# 1_123456_01.net
KiCad netlist of a schematic drawn in Altium Designer
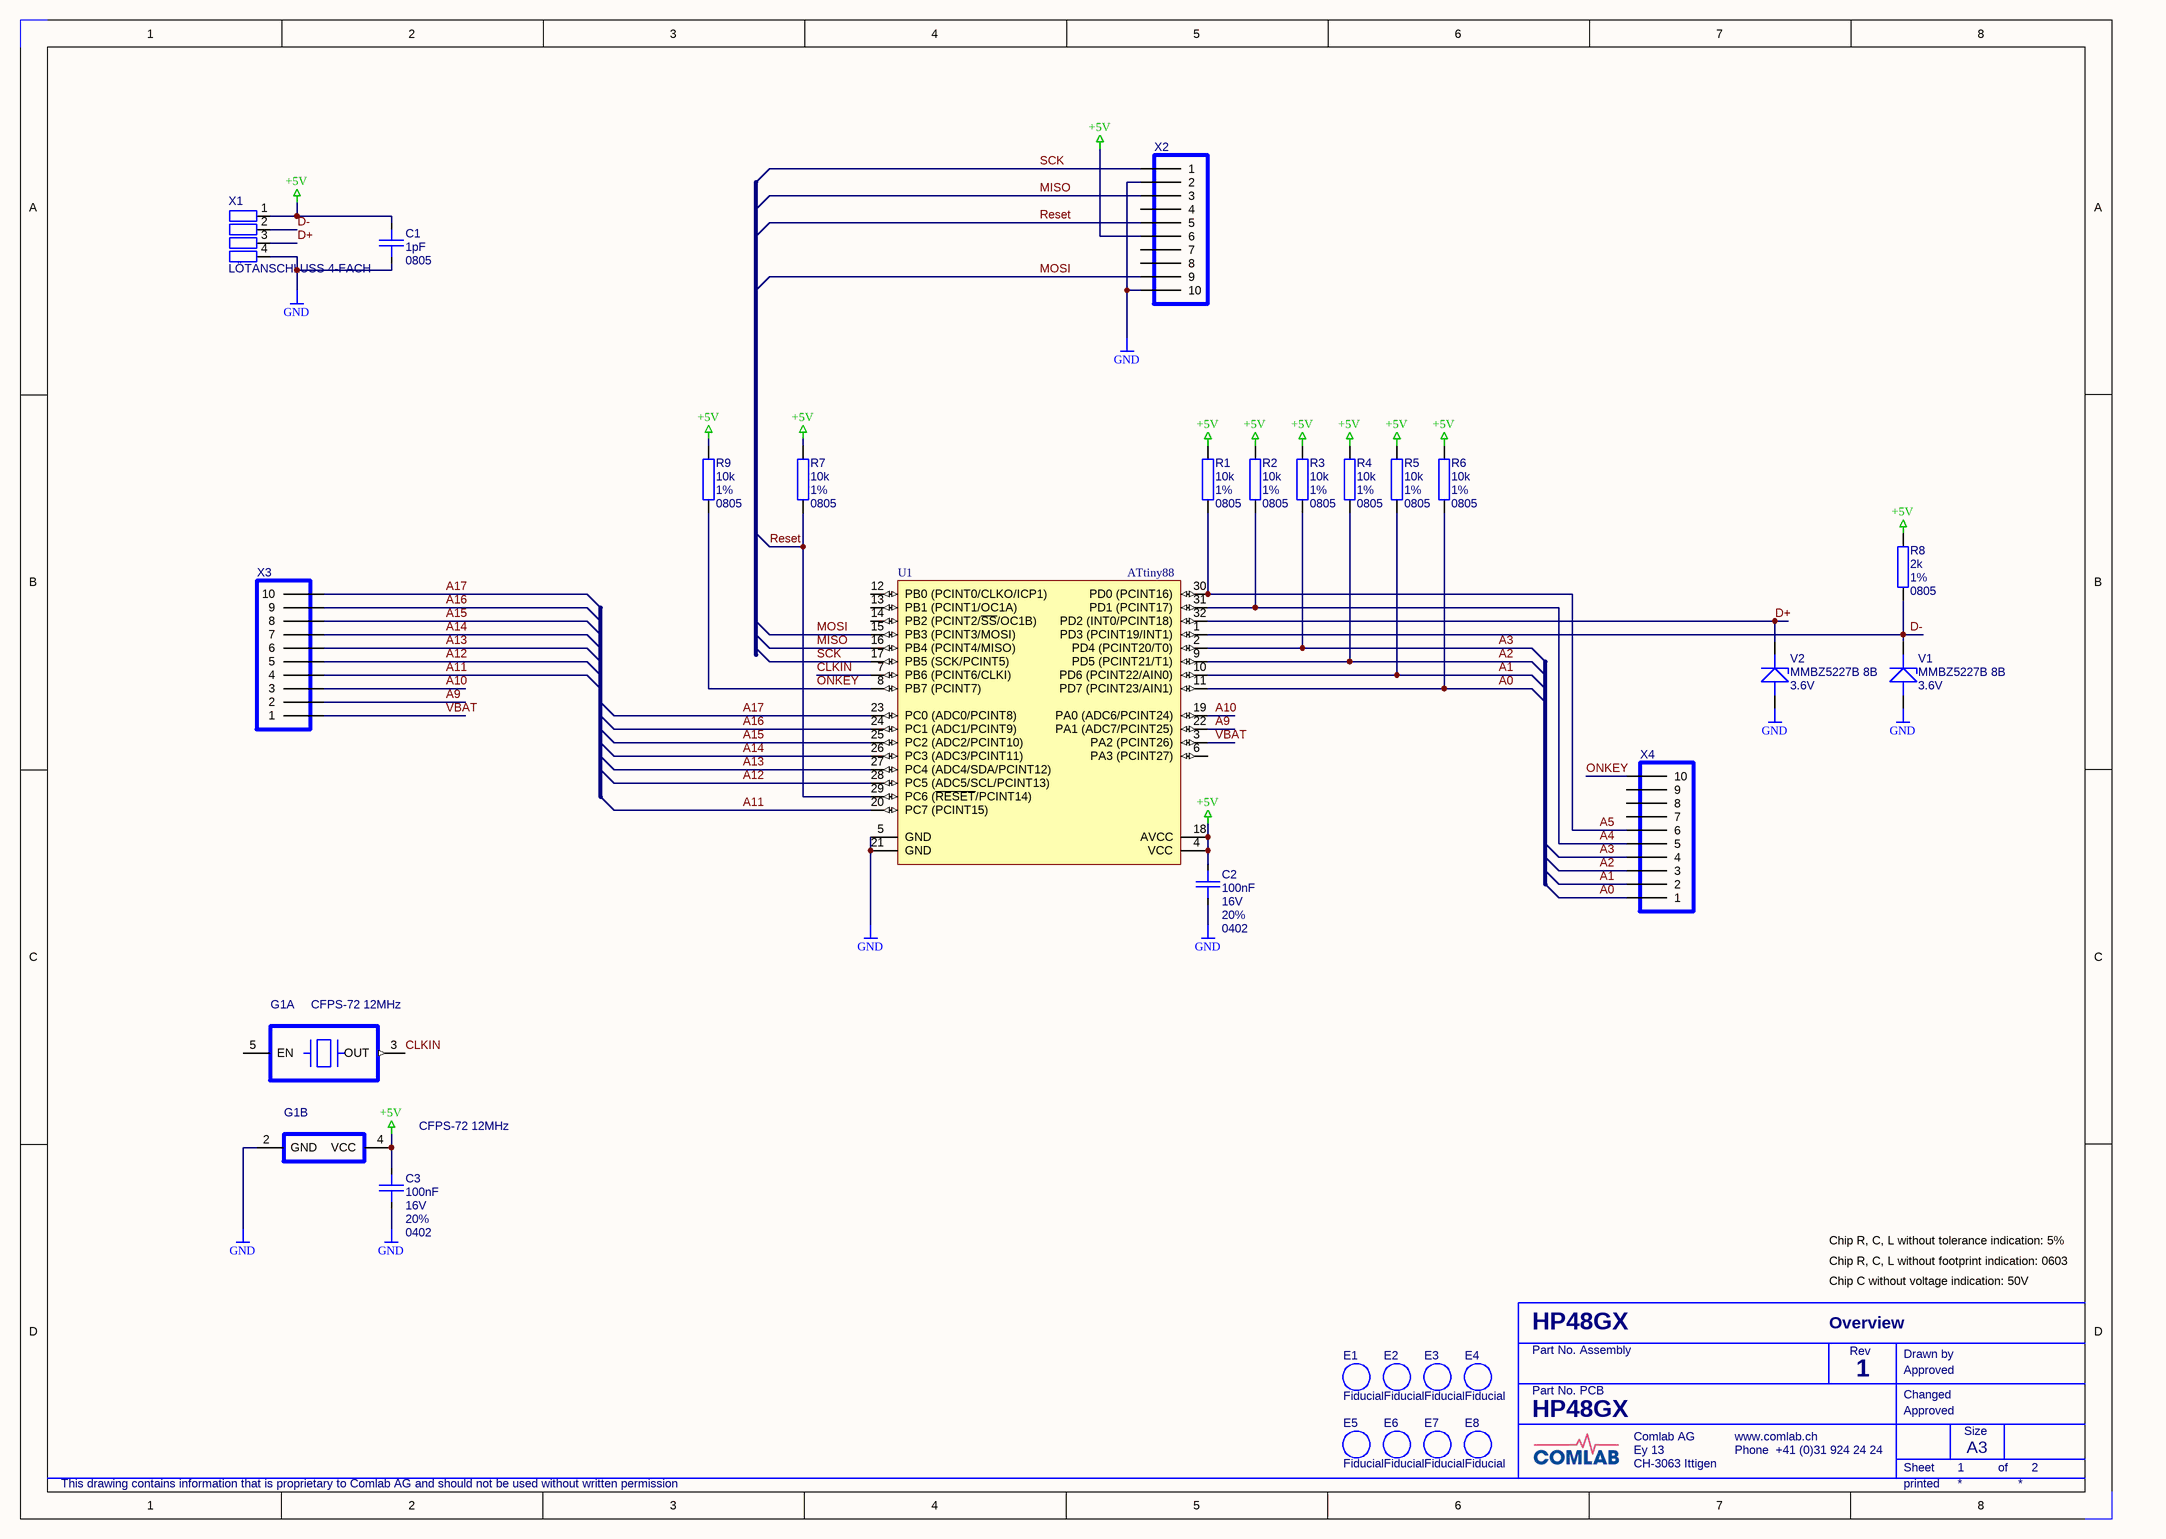
[diagram p0: 1_123456_01.SchDoc]

(export (version "E")
  (design (tool "Eeschema 10.0.6"))
  (components
    (comp (ref "C1")
      (value "1pF")
      (footprint "0805")
      (description "Kond/Chip-Kondensator")
      (libsource (lib "Library Comlab") (part "(1pF  0805  15.00064"))
    )
    (comp (ref "C2")
      (value "100nF")
      (footprint "0402")
      (description "Kond/Chip-Kondensator")
      (fields (field (name "SPANNUNG") "16V") (field (name "TOLERANZ") "20%"))
      (libsource (lib "HP48GX_01_1") (part "1uF  0402  118194"))
    )
    (comp (ref "C3")
      (value "100nF")
      (footprint "0402")
      (description "Kond/Chip-Kondensator")
      (fields (field (name "SPANNUNG") "16V") (field (name "TOLERANZ") "20%"))
      (libsource (lib "HP48GX_01_1") (part "1uF  0402  118194"))
    )
    (comp (ref "E1")
      (value "Fiducial")
      (footprint "ZENTRIER Fiducial")
      (description "Zubehör/Zentriermarke, 2...8x diagonal auf jedem Print")
      (libsource (lib "Library Comlab") (part "ZENTRIERMARKE Fiducial"))
    )
    (comp (ref "E2")
      (value "Fiducial")
      (footprint "ZENTRIER Fiducial")
      (description "Zubehör/Zentriermarke, 2...8x diagonal auf jedem Print")
      (libsource (lib "Library Comlab") (part "ZENTRIERMARKE Fiducial"))
    )
    (comp (ref "E3")
      (value "Fiducial")
      (footprint "ZENTRIER Fiducial")
      (description "Zubehör/Zentriermarke, 2...8x diagonal auf jedem Print")
      (libsource (lib "Library Comlab") (part "ZENTRIERMARKE Fiducial"))
    )
    (comp (ref "E4")
      (value "Fiducial")
      (footprint "ZENTRIER Fiducial")
      (description "Zubehör/Zentriermarke, 2...8x diagonal auf jedem Print")
      (libsource (lib "Library Comlab") (part "ZENTRIERMARKE Fiducial"))
    )
    (comp (ref "E5")
      (value "Fiducial")
      (footprint "ZENTRIER Fiducial")
      (description "Zubehör/Zentriermarke, 2...8x diagonal auf jedem Print")
      (libsource (lib "Library Comlab") (part "ZENTRIERMARKE Fiducial"))
    )
    (comp (ref "E6")
      (value "Fiducial")
      (footprint "ZENTRIER Fiducial")
      (description "Zubehör/Zentriermarke, 2...8x diagonal auf jedem Print")
      (libsource (lib "Library Comlab") (part "ZENTRIERMARKE Fiducial"))
    )
    (comp (ref "E7")
      (value "Fiducial")
      (footprint "ZENTRIER Fiducial")
      (description "Zubehör/Zentriermarke, 2...8x diagonal auf jedem Print")
      (libsource (lib "Library Comlab") (part "ZENTRIERMARKE Fiducial"))
    )
    (comp (ref "E8")
      (value "Fiducial")
      (footprint "ZENTRIER Fiducial")
      (description "Zubehör/Zentriermarke, 2...8x diagonal auf jedem Print")
      (libsource (lib "Library Comlab") (part "ZENTRIERMARKE Fiducial"))
    )
    (comp (ref "G1")
      (value "CFPS-72 12MHz")
      (footprint "TW0203A")
      (description "RF/OSZI")
      (libsource (lib "") (part "OSZI{colon} 8MHz TW0203  TW0203A  117861_1"))
    )
    (comp (ref "R1")
      (value "10k")
      (footprint "0805")
      (description "Wid/Chip-Widerstand")
      (fields (field (name "TOLERANZ") "1%"))
      (libsource (lib "Library Comlab") (part "(1K  0805  14.00130"))
    )
    (comp (ref "R2")
      (value "10k")
      (footprint "0805")
      (description "Wid/Chip-Widerstand")
      (fields (field (name "TOLERANZ") "1%"))
      (libsource (lib "Library Comlab") (part "(1K  0805  14.00130"))
    )
    (comp (ref "R3")
      (value "10k")
      (footprint "0805")
      (description "Wid/Chip-Widerstand")
      (fields (field (name "TOLERANZ") "1%"))
      (libsource (lib "Library Comlab") (part "(1K  0805  14.00130"))
    )
    (comp (ref "R4")
      (value "10k")
      (footprint "0805")
      (description "Wid/Chip-Widerstand")
      (fields (field (name "TOLERANZ") "1%"))
      (libsource (lib "Library Comlab") (part "(1K  0805  14.00130"))
    )
    (comp (ref "R5")
      (value "10k")
      (footprint "0805")
      (description "Wid/Chip-Widerstand")
      (fields (field (name "TOLERANZ") "1%"))
      (libsource (lib "Library Comlab") (part "(1K  0805  14.00130"))
    )
    (comp (ref "R6")
      (value "10k")
      (footprint "0805")
      (description "Wid/Chip-Widerstand")
      (fields (field (name "TOLERANZ") "1%"))
      (libsource (lib "Library Comlab") (part "(1K  0805  14.00130"))
    )
    (comp (ref "R7")
      (value "10k")
      (footprint "0805")
      (description "Wid/Chip-Widerstand")
      (fields (field (name "TOLERANZ") "1%"))
      (libsource (lib "Library Comlab") (part "(1K  0805  14.00130"))
    )
    (comp (ref "R8")
      (value "2k")
      (footprint "0805")
      (description "Wid/Chip-Widerstand")
      (fields (field (name "TOLERANZ") "1%"))
      (libsource (lib "Library Comlab") (part "(1K  0805  14.00130"))
    )
    (comp (ref "R9")
      (value "10k")
      (footprint "0805")
      (description "Wid/Chip-Widerstand")
      (fields (field (name "TOLERANZ") "1%"))
      (libsource (lib "Library Comlab") (part "(1K  0805  14.00130"))
    )
    (comp (ref "U1")
      (value "ATtiny88")
      (footprint "32A_N")
      (fields (field (name "PUBLISHER") "Altium Limited"))
      (libsource (lib "HP48GX_01") (part "ATtiny88-AU"))
    )
    (comp (ref "V1")
      (value "MMBZ5227B 8B")
      (footprint "SOT-23")
      (description "Semidisc/Zener-Diode")
      (fields (field (name "ZENER-SPANNUNG") "3.6V"))
      (libsource (lib "Library Comlab") (part "MMBZ5227B 8B  SOT-23  10.00022"))
    )
    (comp (ref "V2")
      (value "MMBZ5227B 8B")
      (footprint "SOT-23")
      (description "Semidisc/Zener-Diode")
      (fields (field (name "ZENER-SPANNUNG") "3.6V"))
      (libsource (lib "Library Comlab") (part "MMBZ5227B 8B  SOT-23  10.00022"))
    )
    (comp (ref "X1")
      (value "LÖTANSCHLUSS 4-FACH")
      (footprint "LÖTANSCHLUSS 4X 2X5MM")
      (description "Stecker/Lötanschluss")
      (libsource (lib "Library Comlab") (part "LÖTANSCHLUSS 4-FACH  LÖTANSCHLUSS 4X 2X5MM  -"))
    )
    (comp (ref "X2")
      (value "Header 10P")
      (footprint "XHEAD2R10PR1.27MMSB SMD")
      (description "Stecker/Headerf Stehend")
      (libsource (lib "") (part "HEADER10P  XHEAD2R20PR0.5SB  119896_2"))
    )
    (comp (ref "X3")
      (value "Header 10P")
      (footprint "XHEAD2R10PR1.27MMSB SMD")
      (description "Stecker/Headerf Stehend")
      (libsource (lib "") (part "HEADER10P  XHEAD2R20PR0.5SB  119896_1"))
    )
    (comp (ref "X4")
      (value "Header 10P")
      (footprint "XHEAD2R10PR1.27MMSB SMD")
      (description "Stecker/Headerf Stehend")
      (libsource (lib "HP48GX_01_2") (part "HEADER10P  XHEAD2R20PR0.5SB  119896"))
    )
  )
  (nets
    (net (code "1") (name "+5V") (class "Default")
      (node (ref "C1") (pin "1") (pinfunction "1_1") (pintype "passive"))
      (node (ref "C2") (pin "1") (pinfunction "1_1") (pintype "passive"))
      (node (ref "C3") (pin "1") (pinfunction "1_1") (pintype "passive"))
      (node (ref "G1") (pin "4") (pinfunction "VCC_4") (pintype "power_in"))
      (node (ref "R1") (pin "2") (pinfunction "2_2") (pintype "passive"))
      (node (ref "R2") (pin "2") (pinfunction "2_2") (pintype "passive"))
      (node (ref "R3") (pin "2") (pinfunction "2_2") (pintype "passive"))
      (node (ref "R4") (pin "2") (pinfunction "2_2") (pintype "passive"))
      (node (ref "R5") (pin "2") (pinfunction "2_2") (pintype "passive"))
      (node (ref "R6") (pin "2") (pinfunction "2_2") (pintype "passive"))
      (node (ref "R7") (pin "2") (pinfunction "2_2") (pintype "passive"))
      (node (ref "R8") (pin "2") (pinfunction "2_2") (pintype "passive"))
      (node (ref "R9") (pin "2") (pinfunction "2_2") (pintype "passive"))
      (node (ref "U1") (pin "18") (pinfunction "AVCC_18") (pintype "power_in"))
      (node (ref "U1") (pin "4") (pinfunction "VCC_4") (pintype "power_in"))
      (node (ref "X1") (pin "1") (pinfunction "1_1") (pintype "passive"))
      (node (ref "X2") (pin "6") (pinfunction "6_6") (pintype "passive"))
    )
    (net (code "2") (name "/A0") (class "Default")
      (node (ref "R6") (pin "1") (pinfunction "1_1") (pintype "passive"))
      (node (ref "U1") (pin "11") (pinfunction "PD7_(PCINT23/AIN1)_11") (pintype "bidirectional"))
      (node (ref "X4") (pin "1") (pinfunction "1_1") (pintype "passive"))
    )
    (net (code "3") (name "/A1") (class "Default")
      (node (ref "R5") (pin "1") (pinfunction "1_1") (pintype "passive"))
      (node (ref "U1") (pin "10") (pinfunction "PD6_(PCINT22/AIN0)_10") (pintype "bidirectional"))
      (node (ref "X4") (pin "2") (pinfunction "2_2") (pintype "passive"))
    )
    (net (code "4") (name "/A2") (class "Default")
      (node (ref "R4") (pin "1") (pinfunction "1_1") (pintype "passive"))
      (node (ref "U1") (pin "9") (pinfunction "PD5_(PCINT21/T1)_9") (pintype "bidirectional"))
      (node (ref "X4") (pin "3") (pinfunction "3_3") (pintype "passive"))
    )
    (net (code "5") (name "/A3") (class "Default")
      (node (ref "R3") (pin "1") (pinfunction "1_1") (pintype "passive"))
      (node (ref "U1") (pin "2") (pinfunction "PD4_(PCINT20/T0)_2") (pintype "bidirectional"))
      (node (ref "X4") (pin "4") (pinfunction "4_4") (pintype "passive"))
    )
    (net (code "6") (name "/A4") (class "Default")
      (node (ref "R2") (pin "1") (pinfunction "1_1") (pintype "passive"))
      (node (ref "U1") (pin "31") (pinfunction "PD1_(PCINT17)_31") (pintype "bidirectional"))
      (node (ref "X4") (pin "5") (pinfunction "5_5") (pintype "passive"))
    )
    (net (code "7") (name "/A5") (class "Default")
      (node (ref "R1") (pin "1") (pinfunction "1_1") (pintype "passive"))
      (node (ref "U1") (pin "30") (pinfunction "PD0_(PCINT16)_30") (pintype "bidirectional"))
      (node (ref "X4") (pin "6") (pinfunction "6_6") (pintype "passive"))
    )
    (net (code "8") (name "/A9") (class "Default")
      (node (ref "U1") (pin "22") (pinfunction "PA1_(ADC7/PCINT25)_22") (pintype "bidirectional"))
      (node (ref "X3") (pin "2") (pinfunction "2_2") (pintype "passive"))
    )
    (net (code "9") (name "/A10") (class "Default")
      (node (ref "U1") (pin "19") (pinfunction "PA0_(ADC6/PCINT24)_19") (pintype "bidirectional"))
      (node (ref "X3") (pin "3") (pinfunction "3_3") (pintype "passive"))
    )
    (net (code "10") (name "/A11") (class "Default")
      (node (ref "U1") (pin "20") (pinfunction "PC7_(PCINT15)_20") (pintype "bidirectional"))
      (node (ref "X3") (pin "4") (pinfunction "4_4") (pintype "passive"))
    )
    (net (code "11") (name "/A12") (class "Default")
      (node (ref "U1") (pin "28") (pinfunction "PC5_(ADC5/SCL/PCINT13)_28") (pintype "bidirectional"))
      (node (ref "X3") (pin "5") (pinfunction "5_5") (pintype "passive"))
    )
    (net (code "12") (name "/A13") (class "Default")
      (node (ref "U1") (pin "27") (pinfunction "PC4_(ADC4/SDA/PCINT12)_27") (pintype "bidirectional"))
      (node (ref "X3") (pin "6") (pinfunction "6_6") (pintype "passive"))
    )
    (net (code "13") (name "/A14") (class "Default")
      (node (ref "U1") (pin "26") (pinfunction "PC3_(ADC3/PCINT11)_26") (pintype "bidirectional"))
      (node (ref "X3") (pin "7") (pinfunction "7_7") (pintype "passive"))
    )
    (net (code "14") (name "/A15") (class "Default")
      (node (ref "U1") (pin "25") (pinfunction "PC2_(ADC2/PCINT10)_25") (pintype "bidirectional"))
      (node (ref "X3") (pin "8") (pinfunction "8_8") (pintype "passive"))
    )
    (net (code "15") (name "/A16") (class "Default")
      (node (ref "U1") (pin "24") (pinfunction "PC1_(ADC1/PCINT9)_24") (pintype "bidirectional"))
      (node (ref "X3") (pin "9") (pinfunction "9_9") (pintype "passive"))
    )
    (net (code "16") (name "/A17") (class "Default")
      (node (ref "U1") (pin "23") (pinfunction "PC0_(ADC0/PCINT8)_23") (pintype "bidirectional"))
      (node (ref "X3") (pin "10") (pinfunction "10_10") (pintype "passive"))
    )
    (net (code "17") (name "/CLKIN") (class "Default")
      (node (ref "G1") (pin "3") (pinfunction "OUT_3") (pintype "output"))
      (node (ref "U1") (pin "7") (pinfunction "PB6_(PCINT6/CLKI)_7") (pintype "bidirectional"))
    )
    (net (code "18") (name "/D+") (class "Default")
      (node (ref "U1") (pin "32") (pinfunction "PD2_(INT0/PCINT18)_32") (pintype "bidirectional"))
      (node (ref "V2") (pin "3") (pinfunction "k_3") (pintype "passive"))
      (node (ref "X1") (pin "3") (pinfunction "3_3") (pintype "passive"))
    )
    (net (code "19") (name "/D-") (class "Default")
      (node (ref "R8") (pin "1") (pinfunction "1_1") (pintype "passive"))
      (node (ref "U1") (pin "1") (pinfunction "PD3_(PCINT19/INT1)_1") (pintype "bidirectional"))
      (node (ref "V1") (pin "3") (pinfunction "k_3") (pintype "passive"))
      (node (ref "X1") (pin "2") (pinfunction "2_2") (pintype "passive"))
    )
    (net (code "20") (name "/MISO") (class "Default")
      (node (ref "U1") (pin "16") (pinfunction "PB4_(PCINT4/MISO)_16") (pintype "bidirectional"))
      (node (ref "X2") (pin "3") (pinfunction "3_3") (pintype "passive"))
    )
    (net (code "21") (name "/MOSI") (class "Default")
      (node (ref "U1") (pin "15") (pinfunction "PB3_(PCINT3/MOSI)_15") (pintype "bidirectional"))
      (node (ref "X2") (pin "9") (pinfunction "9_9") (pintype "passive"))
    )
    (net (code "22") (name "/ONKEY") (class "Default")
      (node (ref "R9") (pin "1") (pinfunction "1_1") (pintype "passive"))
      (node (ref "U1") (pin "8") (pinfunction "PB7_(PCINT7)_8") (pintype "bidirectional"))
      (node (ref "X4") (pin "10") (pinfunction "10_10") (pintype "passive"))
    )
    (net (code "23") (name "/Reset") (class "Default")
      (node (ref "R7") (pin "1") (pinfunction "1_1") (pintype "passive"))
      (node (ref "U1") (pin "29") (pinfunction "PC6_(~{RESET}/PCINT14)_29") (pintype "bidirectional"))
      (node (ref "X2") (pin "5") (pinfunction "5_5") (pintype "passive"))
    )
    (net (code "24") (name "/SCK") (class "Default")
      (node (ref "U1") (pin "17") (pinfunction "PB5_(SCK/PCINT5)_17") (pintype "bidirectional"))
      (node (ref "X2") (pin "1") (pinfunction "1_1") (pintype "passive"))
    )
    (net (code "25") (name "/VBAT") (class "Default")
      (node (ref "U1") (pin "3") (pinfunction "PA2_(PCINT26)_3") (pintype "bidirectional"))
      (node (ref "X3") (pin "1") (pinfunction "1_1") (pintype "passive"))
    )
    (net (code "26") (name "GND") (class "Default")
      (node (ref "C1") (pin "2") (pinfunction "2_2") (pintype "passive"))
      (node (ref "C2") (pin "2") (pinfunction "2_2") (pintype "passive"))
      (node (ref "C3") (pin "2") (pinfunction "2_2") (pintype "passive"))
      (node (ref "G1") (pin "2") (pinfunction "GND_2") (pintype "power_in"))
      (node (ref "U1") (pin "21") (pinfunction "GND_21") (pintype "power_in"))
      (node (ref "U1") (pin "5") (pinfunction "GND_5") (pintype "power_in"))
      (node (ref "V1") (pin "1") (pinfunction "a_1") (pintype "passive"))
      (node (ref "V2") (pin "1") (pinfunction "a_1") (pintype "passive"))
      (node (ref "X1") (pin "4") (pinfunction "4_4") (pintype "passive"))
      (node (ref "X2") (pin "10") (pinfunction "10_10") (pintype "passive"))
      (node (ref "X2") (pin "2") (pinfunction "2_2") (pintype "passive"))
    )
    (net (code "27") (name "unconnected-(G1A-EN-Pad5)") (class "Default")
      (node (ref "G1") (pin "5") (pinfunction "EN_5") (pintype "passive"))
    )
    (net (code "28") (name "unconnected-(U1-PA3_(PCINT27)-Pad6)") (class "Default")
      (node (ref "U1") (pin "6") (pinfunction "PA3_(PCINT27)_6") (pintype "bidirectional"))
    )
    (net (code "29") (name "unconnected-(U1-PB0_(PCINT0{slash}CLKO{slash}ICP1)-Pad12)") (class "Default")
      (node (ref "U1") (pin "12") (pinfunction "PB0_(PCINT0/CLKO/ICP1)_12") (pintype "bidirectional"))
    )
    (net (code "30") (name "unconnected-(U1-PB1_(PCINT1{slash}OC1A)-Pad13)") (class "Default")
      (node (ref "U1") (pin "13") (pinfunction "PB1_(PCINT1/OC1A)_13") (pintype "bidirectional"))
    )
    (net (code "31") (name "unconnected-(U1-PB2_(PCINT2{slash}~{SS}{slash}OC1B)-Pad14)") (class "Default")
      (node (ref "U1") (pin "14") (pinfunction "PB2_(PCINT2/~{SS}/OC1B)_14") (pintype "bidirectional"))
    )
    (net (code "32") (name "unconnected-(X2-Pad4)") (class "Default")
      (node (ref "X2") (pin "4") (pinfunction "4_4") (pintype "passive"))
    )
    (net (code "33") (name "unconnected-(X2-Pad7)") (class "Default")
      (node (ref "X2") (pin "7") (pinfunction "7_7") (pintype "passive"))
    )
    (net (code "34") (name "unconnected-(X2-Pad8)") (class "Default")
      (node (ref "X2") (pin "8") (pinfunction "8_8") (pintype "passive"))
    )
    (net (code "35") (name "unconnected-(X4-Pad7)") (class "Default")
      (node (ref "X4") (pin "7") (pinfunction "7_7") (pintype "passive"))
    )
    (net (code "36") (name "unconnected-(X4-Pad8)") (class "Default")
      (node (ref "X4") (pin "8") (pinfunction "8_8") (pintype "passive"))
    )
    (net (code "37") (name "unconnected-(X4-Pad9)") (class "Default")
      (node (ref "X4") (pin "9") (pinfunction "9_9") (pintype "passive"))
    )
  )
)
